# OUTPUT.net
KiCad netlist of a schematic drawn in Altium Designer
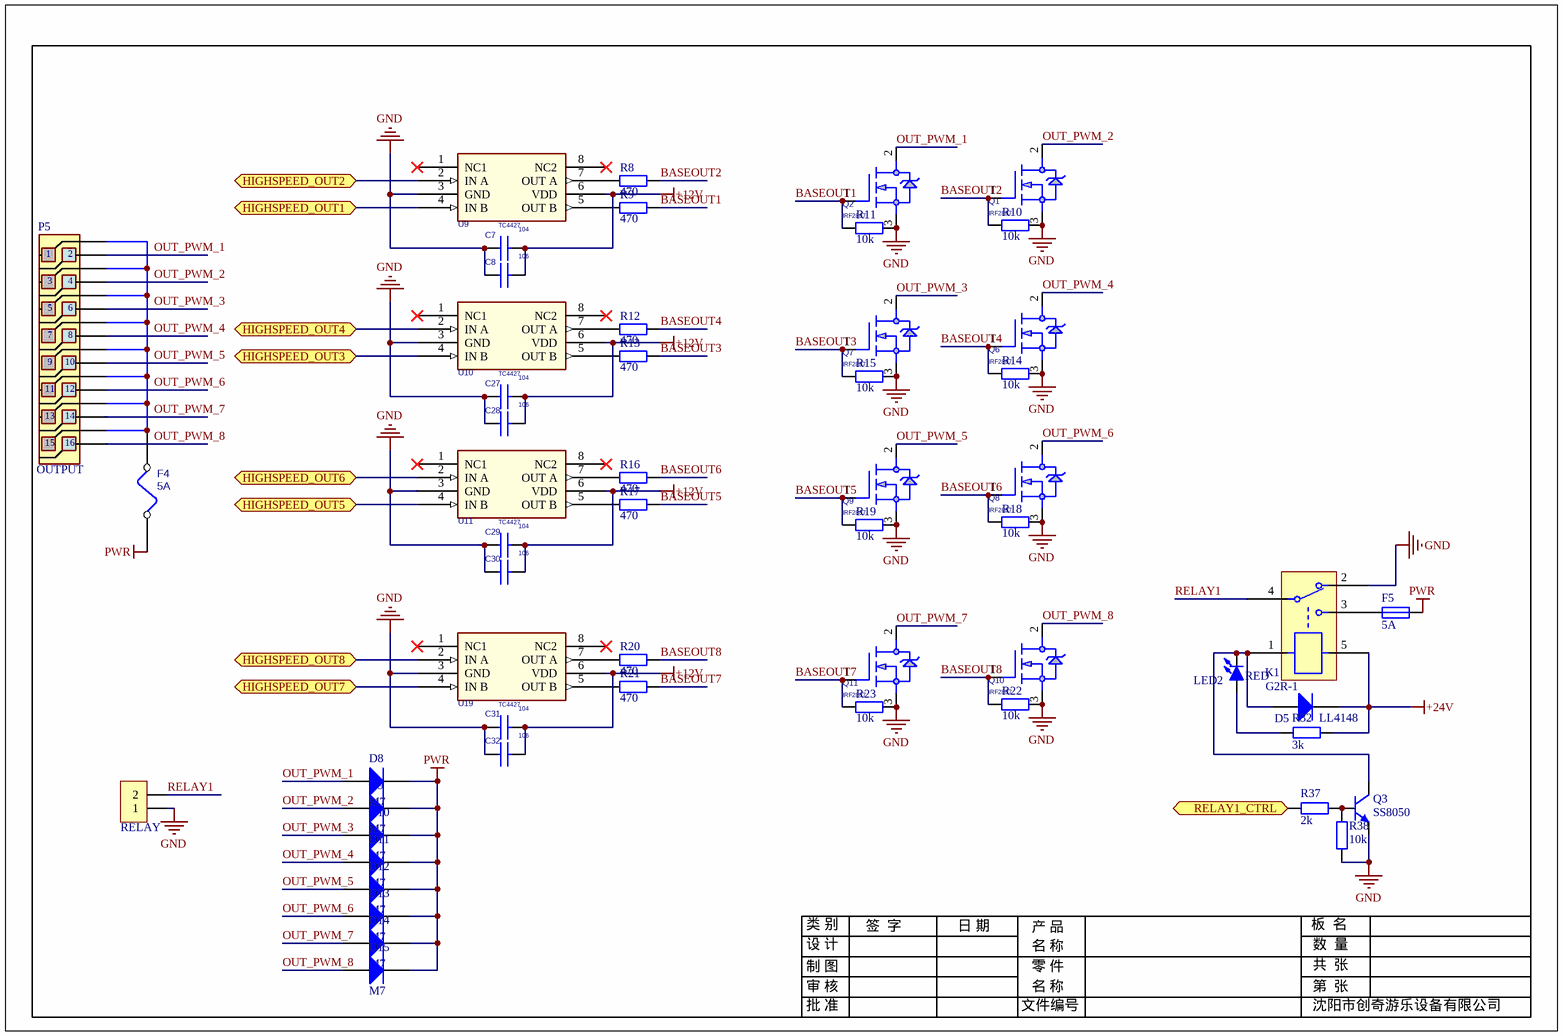
[diagram p0: OUTPUT.SchDoc]

(export (version "E")
  (design (tool "Eeschema 10.0.6"))
  (components
    (comp (ref "C7") (value "104") (footprint "C 0805") (libsource (lib "*") (part "CAP NP")))
    (comp (ref "C8") (value "106") (footprint "C 0805") (libsource (lib "*") (part "CAP NP")))
    (comp (ref "C27") (value "104") (footprint "C 0805") (libsource (lib "*") (part "CAP NP")))
    (comp (ref "C28") (value "106") (footprint "C 0805") (libsource (lib "*") (part "CAP NP")))
    (comp (ref "C29") (value "104") (footprint "C 0805") (libsource (lib "*") (part "CAP NP")))
    (comp (ref "C30") (value "106") (footprint "C 0805") (libsource (lib "*") (part "CAP NP")))
    (comp (ref "C31") (value "104") (footprint "C 0805") (libsource (lib "*") (part "CAP NP")))
    (comp (ref "C32") (value "106") (footprint "C 0805") (libsource (lib "*") (part "CAP NP")))
    (comp (ref "D5") (value "LL4148") (footprint "MINI_MELF (LL34)") (libsource (lib "any") (part "Diode")))
    (comp (ref "D8") (value "M7") (footprint "SMA") (libsource (lib "any") (part "Diode")))
    (comp (ref "D9") (value "M7") (footprint "SMA") (libsource (lib "any") (part "Diode")))
    (comp (ref "D10") (value "M7") (footprint "SMA") (libsource (lib "any") (part "Diode")))
    (comp (ref "D11") (value "M7") (footprint "SMA") (libsource (lib "any") (part "Diode")))
    (comp (ref "D12") (value "M7") (footprint "SMA") (libsource (lib "any") (part "Diode")))
    (comp (ref "D13") (value "M7") (footprint "SMA") (libsource (lib "any") (part "Diode")))
    (comp (ref "D14") (value "M7") (footprint "SMA") (libsource (lib "any") (part "Diode")))
    (comp (ref "D15") (value "M7") (footprint "SMA") (libsource (lib "any") (part "Diode")))
    (comp (ref "F4") (value "5A") (libsource (lib "*") (part "FUSE")))
    (comp (ref "F5")
      (value "5A")
      (footprint "FUSEe-CAR")
      (description "Fuse")
      (libsource (lib "*") (part "FUSE1"))
    )
    (comp (ref "K1") (value "G2R-1") (footprint "RELAY_OMRON_G2R") (libsource (lib "any") (part "Relay2")))
    (comp (ref "LED2")
      (value "RED")
      (footprint "LED 3MM-R")
      (description "贴片LED")
      (fields (field (name "版权归属") "源创客"))
      (libsource (lib "LED") (part "LED-SMD"))
    )
    (comp (ref "P5")
      (value "OUTPUT")
      (footprint "557-2x8")
      (description "接插件")
      (libsource (lib "Connectors") (part "557-2x8"))
    )
    (comp (ref "Q1") (value "IRF2807") (footprint "TO220A") (libsource (lib "*") (part "MOSFET N-Channel")))
    (comp (ref "Q2") (value "IRF2807") (footprint "TO220A") (libsource (lib "*") (part "MOSFET N-Channel")))
    (comp (ref "Q3")
      (value "SS8050")
      (footprint "SOT23-3N")
      (description "高频放大-NPN型")
      (fields (field (name "版权归属") "源创客"))
      (libsource (lib "三极管") (part "8050-SMD"))
    )
    (comp (ref "Q6") (value "IRF2807") (footprint "TO220A") (libsource (lib "*") (part "MOSFET N-Channel")))
    (comp (ref "Q7") (value "IRF2807") (footprint "TO220A") (libsource (lib "*") (part "MOSFET N-Channel")))
    (comp (ref "Q8") (value "IRF2807") (footprint "TO220A") (libsource (lib "*") (part "MOSFET N-Channel")))
    (comp (ref "Q9") (value "IRF2807") (footprint "TO220A") (libsource (lib "*") (part "MOSFET N-Channel")))
    (comp (ref "Q10") (value "IRF2807") (footprint "TO220A") (libsource (lib "*") (part "MOSFET N-Channel")))
    (comp (ref "Q11") (value "IRF2807") (footprint "TO220A") (libsource (lib "*") (part "MOSFET N-Channel")))
    (comp (ref "R8") (value "470") (footprint "R 0805") (libsource (lib "any") (part "Res1")))
    (comp (ref "R9") (value "470") (footprint "R 0805") (libsource (lib "any") (part "Res1")))
    (comp (ref "R10") (value "10k") (footprint "R 0805") (libsource (lib "any") (part "Res1")))
    (comp (ref "R11") (value "10k") (footprint "R 0805") (libsource (lib "any") (part "Res1")))
    (comp (ref "R12") (value "470") (footprint "R 0805") (libsource (lib "any") (part "Res1")))
    (comp (ref "R13") (value "470") (footprint "R 0805") (libsource (lib "any") (part "Res1")))
    (comp (ref "R14") (value "10k") (footprint "R 0805") (libsource (lib "any") (part "Res1")))
    (comp (ref "R15") (value "10k") (footprint "R 0805") (libsource (lib "any") (part "Res1")))
    (comp (ref "R16") (value "470") (footprint "R 0805") (libsource (lib "any") (part "Res1")))
    (comp (ref "R17") (value "470") (footprint "R 0805") (libsource (lib "any") (part "Res1")))
    (comp (ref "R18") (value "10k") (footprint "R 0805") (libsource (lib "any") (part "Res1")))
    (comp (ref "R19") (value "10k") (footprint "R 0805") (libsource (lib "any") (part "Res1")))
    (comp (ref "R20") (value "470") (footprint "R 0805") (libsource (lib "any") (part "Res1")))
    (comp (ref "R21") (value "470") (footprint "R 0805") (libsource (lib "any") (part "Res1")))
    (comp (ref "R22") (value "10k") (footprint "R 0805") (libsource (lib "any") (part "Res1")))
    (comp (ref "R23") (value "10k") (footprint "R 0805") (libsource (lib "any") (part "Res1")))
    (comp (ref "R32")
      (value "3k")
      (footprint "R 0805")
      (description "贴片电阻")
      (fields (field (name "版权归属") "源创客"))
      (libsource (lib "电阻-电容-电感") (part "R"))
    )
    (comp (ref "R37")
      (value "2k")
      (footprint "R 0805")
      (description "贴片电阻")
      (fields (field (name "版权归属") "源创客"))
      (libsource (lib "电阻-电容-电感") (part "R"))
    )
    (comp (ref "R38")
      (value "10k")
      (footprint "R 0805")
      (description "贴片电阻")
      (fields (field (name "版权归属") "源创客"))
      (libsource (lib "电阻-电容-电感") (part "R"))
    )
    (comp (ref "RELAY")
      (value "AUX")
      (footprint "557-2X1")
      (description "2P接插件")
      (fields (field (name "版权归属") "源创客"))
      (libsource (lib "接插件") (part "Header 2"))
    )
    (comp (ref "U9") (value "TC4427") (footprint "SO8") (libsource (lib "*") (part "TC4427EPA")))
    (comp (ref "U10") (value "TC4427") (footprint "SO8") (libsource (lib "*") (part "TC4427EPA")))
    (comp (ref "U11") (value "TC4427") (footprint "SO8") (libsource (lib "*") (part "TC4427EPA")))
    (comp (ref "U19") (value "TC4427") (footprint "SO8") (libsource (lib "*") (part "TC4427EPA")))
  )
  (nets
    (net (code "1") (name "+12V") (class "Default")
      (node (ref "C27") (pin "2") (pinfunction "2_2") (pintype "passive"))
      (node (ref "C28") (pin "2") (pinfunction "2_2") (pintype "passive"))
      (node (ref "C29") (pin "2") (pinfunction "2_2") (pintype "passive"))
      (node (ref "C30") (pin "2") (pinfunction "2_2") (pintype "passive"))
      (node (ref "C31") (pin "2") (pinfunction "2_2") (pintype "passive"))
      (node (ref "C32") (pin "2") (pinfunction "2_2") (pintype "passive"))
      (node (ref "C7") (pin "2") (pinfunction "2_2") (pintype "passive"))
      (node (ref "C8") (pin "2") (pinfunction "2_2") (pintype "passive"))
      (node (ref "U10") (pin "6") (pinfunction "VDD_6") (pintype "power_in"))
      (node (ref "U11") (pin "6") (pinfunction "VDD_6") (pintype "power_in"))
      (node (ref "U19") (pin "6") (pinfunction "VDD_6") (pintype "power_in"))
      (node (ref "U9") (pin "6") (pinfunction "VDD_6") (pintype "power_in"))
    )
    (net (code "2") (name "+24V") (class "Default")
      (node (ref "D5") (pin "2") (pinfunction "2_2") (pintype "passive"))
      (node (ref "K1") (pin "5") (pinfunction "5_5") (pintype "passive"))
      (node (ref "R32") (pin "1") (pinfunction "1_1") (pintype "passive"))
    )
    (net (code "3") (name "/BASEOUT1") (class "Default")
      (node (ref "Q2") (pin "1") (pinfunction "G_1") (pintype "passive"))
      (node (ref "R11") (pin "1") (pinfunction "1_1") (pintype "passive"))
      (node (ref "R9") (pin "2") (pinfunction "2_2") (pintype "passive"))
    )
    (net (code "4") (name "/BASEOUT2") (class "Default")
      (node (ref "Q1") (pin "1") (pinfunction "G_1") (pintype "passive"))
      (node (ref "R10") (pin "1") (pinfunction "1_1") (pintype "passive"))
      (node (ref "R8") (pin "2") (pinfunction "2_2") (pintype "passive"))
    )
    (net (code "5") (name "/BASEOUT3") (class "Default")
      (node (ref "Q7") (pin "1") (pinfunction "G_1") (pintype "passive"))
      (node (ref "R13") (pin "2") (pinfunction "2_2") (pintype "passive"))
      (node (ref "R15") (pin "1") (pinfunction "1_1") (pintype "passive"))
    )
    (net (code "6") (name "/BASEOUT4") (class "Default")
      (node (ref "Q6") (pin "1") (pinfunction "G_1") (pintype "passive"))
      (node (ref "R12") (pin "2") (pinfunction "2_2") (pintype "passive"))
      (node (ref "R14") (pin "1") (pinfunction "1_1") (pintype "passive"))
    )
    (net (code "7") (name "/BASEOUT5") (class "Default")
      (node (ref "Q9") (pin "1") (pinfunction "G_1") (pintype "passive"))
      (node (ref "R17") (pin "2") (pinfunction "2_2") (pintype "passive"))
      (node (ref "R19") (pin "1") (pinfunction "1_1") (pintype "passive"))
    )
    (net (code "8") (name "/BASEOUT6") (class "Default")
      (node (ref "Q8") (pin "1") (pinfunction "G_1") (pintype "passive"))
      (node (ref "R16") (pin "2") (pinfunction "2_2") (pintype "passive"))
      (node (ref "R18") (pin "1") (pinfunction "1_1") (pintype "passive"))
    )
    (net (code "9") (name "/BASEOUT7") (class "Default")
      (node (ref "Q11") (pin "1") (pinfunction "G_1") (pintype "passive"))
      (node (ref "R21") (pin "2") (pinfunction "2_2") (pintype "passive"))
      (node (ref "R23") (pin "1") (pinfunction "1_1") (pintype "passive"))
    )
    (net (code "10") (name "/BASEOUT8") (class "Default")
      (node (ref "Q10") (pin "1") (pinfunction "G_1") (pintype "passive"))
      (node (ref "R20") (pin "2") (pinfunction "2_2") (pintype "passive"))
      (node (ref "R22") (pin "1") (pinfunction "1_1") (pintype "passive"))
    )
    (net (code "11") (name "/HIGHSPEED_OUT1") (class "Default")
      (node (ref "U9") (pin "4") (pinfunction "IN_B_4") (pintype "input"))
    )
    (net (code "12") (name "/HIGHSPEED_OUT2") (class "Default")
      (node (ref "U9") (pin "2") (pinfunction "IN_A_2") (pintype "input"))
    )
    (net (code "13") (name "/HIGHSPEED_OUT3") (class "Default")
      (node (ref "U10") (pin "4") (pinfunction "IN_B_4") (pintype "input"))
    )
    (net (code "14") (name "/HIGHSPEED_OUT4") (class "Default")
      (node (ref "U10") (pin "2") (pinfunction "IN_A_2") (pintype "input"))
    )
    (net (code "15") (name "/HIGHSPEED_OUT5") (class "Default")
      (node (ref "U11") (pin "4") (pinfunction "IN_B_4") (pintype "input"))
    )
    (net (code "16") (name "/HIGHSPEED_OUT6") (class "Default")
      (node (ref "U11") (pin "2") (pinfunction "IN_A_2") (pintype "input"))
    )
    (net (code "17") (name "/HIGHSPEED_OUT7") (class "Default")
      (node (ref "U19") (pin "4") (pinfunction "IN_B_4") (pintype "input"))
    )
    (net (code "18") (name "/HIGHSPEED_OUT8") (class "Default")
      (node (ref "U19") (pin "2") (pinfunction "IN_A_2") (pintype "input"))
    )
    (net (code "19") (name "/OUT_PWM_1") (class "Default")
      (node (ref "D8") (pin "1") (pinfunction "1_1") (pintype "passive"))
      (node (ref "P5") (pin "2") (pinfunction "2_2") (pintype "passive"))
      (node (ref "Q2") (pin "2") (pinfunction "D_2") (pintype "passive"))
    )
    (net (code "20") (name "/OUT_PWM_2") (class "Default")
      (node (ref "D9") (pin "1") (pinfunction "1_1") (pintype "passive"))
      (node (ref "P5") (pin "4") (pinfunction "4_4") (pintype "passive"))
      (node (ref "Q1") (pin "2") (pinfunction "D_2") (pintype "passive"))
    )
    (net (code "21") (name "/OUT_PWM_3") (class "Default")
      (node (ref "D10") (pin "1") (pinfunction "1_1") (pintype "passive"))
      (node (ref "P5") (pin "6") (pinfunction "6_6") (pintype "passive"))
      (node (ref "Q7") (pin "2") (pinfunction "D_2") (pintype "passive"))
    )
    (net (code "22") (name "/OUT_PWM_4") (class "Default")
      (node (ref "D11") (pin "1") (pinfunction "1_1") (pintype "passive"))
      (node (ref "P5") (pin "8") (pinfunction "8_8") (pintype "passive"))
      (node (ref "Q6") (pin "2") (pinfunction "D_2") (pintype "passive"))
    )
    (net (code "23") (name "/OUT_PWM_5") (class "Default")
      (node (ref "D12") (pin "1") (pinfunction "1_1") (pintype "passive"))
      (node (ref "P5") (pin "10") (pinfunction "10_10") (pintype "passive"))
      (node (ref "Q9") (pin "2") (pinfunction "D_2") (pintype "passive"))
    )
    (net (code "24") (name "/OUT_PWM_6") (class "Default")
      (node (ref "D13") (pin "1") (pinfunction "1_1") (pintype "passive"))
      (node (ref "P5") (pin "12") (pinfunction "12_12") (pintype "passive"))
      (node (ref "Q8") (pin "2") (pinfunction "D_2") (pintype "passive"))
    )
    (net (code "25") (name "/OUT_PWM_7") (class "Default")
      (node (ref "D14") (pin "1") (pinfunction "1_1") (pintype "passive"))
      (node (ref "P5") (pin "14") (pinfunction "14_14") (pintype "passive"))
      (node (ref "Q11") (pin "2") (pinfunction "D_2") (pintype "passive"))
    )
    (net (code "26") (name "/OUT_PWM_8") (class "Default")
      (node (ref "D15") (pin "1") (pinfunction "1_1") (pintype "passive"))
      (node (ref "P5") (pin "16") (pinfunction "16_16") (pintype "passive"))
      (node (ref "Q10") (pin "2") (pinfunction "D_2") (pintype "passive"))
    )
    (net (code "27") (name "/RELAY1") (class "Default")
      (node (ref "K1") (pin "4") (pinfunction "4_4") (pintype "passive"))
      (node (ref "RELAY") (pin "2") (pinfunction "2_2") (pintype "passive"))
    )
    (net (code "28") (name "/RELAY1_CTRL") (class "Default")
      (node (ref "R37") (pin "2") (pinfunction "2_2") (pintype "passive"))
    )
    (net (code "29") (name "GND") (class "Default")
      (node (ref "C27") (pin "1") (pinfunction "1_1") (pintype "passive"))
      (node (ref "C28") (pin "1") (pinfunction "1_1") (pintype "passive"))
      (node (ref "C29") (pin "1") (pinfunction "1_1") (pintype "passive"))
      (node (ref "C30") (pin "1") (pinfunction "1_1") (pintype "passive"))
      (node (ref "C31") (pin "1") (pinfunction "1_1") (pintype "passive"))
      (node (ref "C32") (pin "1") (pinfunction "1_1") (pintype "passive"))
      (node (ref "C7") (pin "1") (pinfunction "1_1") (pintype "passive"))
      (node (ref "C8") (pin "1") (pinfunction "1_1") (pintype "passive"))
      (node (ref "K1") (pin "2") (pinfunction "2_2") (pintype "passive"))
      (node (ref "Q1") (pin "3") (pinfunction "S_3") (pintype "passive"))
      (node (ref "Q10") (pin "3") (pinfunction "S_3") (pintype "passive"))
      (node (ref "Q11") (pin "3") (pinfunction "S_3") (pintype "passive"))
      (node (ref "Q2") (pin "3") (pinfunction "S_3") (pintype "passive"))
      (node (ref "Q3") (pin "2") (pinfunction "E_2") (pintype "passive"))
      (node (ref "Q6") (pin "3") (pinfunction "S_3") (pintype "passive"))
      (node (ref "Q7") (pin "3") (pinfunction "S_3") (pintype "passive"))
      (node (ref "Q8") (pin "3") (pinfunction "S_3") (pintype "passive"))
      (node (ref "Q9") (pin "3") (pinfunction "S_3") (pintype "passive"))
      (node (ref "R10") (pin "2") (pinfunction "2_2") (pintype "passive"))
      (node (ref "R11") (pin "2") (pinfunction "2_2") (pintype "passive"))
      (node (ref "R14") (pin "2") (pinfunction "2_2") (pintype "passive"))
      (node (ref "R15") (pin "2") (pinfunction "2_2") (pintype "passive"))
      (node (ref "R18") (pin "2") (pinfunction "2_2") (pintype "passive"))
      (node (ref "R19") (pin "2") (pinfunction "2_2") (pintype "passive"))
      (node (ref "R22") (pin "2") (pinfunction "2_2") (pintype "passive"))
      (node (ref "R23") (pin "2") (pinfunction "2_2") (pintype "passive"))
      (node (ref "R38") (pin "2") (pinfunction "2_2") (pintype "passive"))
      (node (ref "RELAY") (pin "1") (pinfunction "1_1") (pintype "passive"))
      (node (ref "U10") (pin "3") (pinfunction "GND_3") (pintype "power_in"))
      (node (ref "U11") (pin "3") (pinfunction "GND_3") (pintype "power_in"))
      (node (ref "U19") (pin "3") (pinfunction "GND_3") (pintype "power_in"))
      (node (ref "U9") (pin "3") (pinfunction "GND_3") (pintype "power_in"))
    )
    (net (code "30") (name "Net-(F4-Pad2)") (class "Default")
      (node (ref "F4") (pin "2") (pinfunction "2_2") (pintype "passive"))
      (node (ref "P5") (pin "1") (pinfunction "1_1") (pintype "passive"))
      (node (ref "P5") (pin "11") (pinfunction "11_11") (pintype "passive"))
      (node (ref "P5") (pin "13") (pinfunction "13_13") (pintype "passive"))
      (node (ref "P5") (pin "15") (pinfunction "15_15") (pintype "passive"))
      (node (ref "P5") (pin "3") (pinfunction "3_3") (pintype "passive"))
      (node (ref "P5") (pin "5") (pinfunction "5_5") (pintype "passive"))
      (node (ref "P5") (pin "7") (pinfunction "7_7") (pintype "passive"))
      (node (ref "P5") (pin "9") (pinfunction "9_9") (pintype "passive"))
    )
    (net (code "31") (name "Net-(F5-Pad1)") (class "Default")
      (node (ref "F5") (pin "1") (pinfunction "1_1") (pintype "passive"))
      (node (ref "K1") (pin "3") (pinfunction "3_3") (pintype "passive"))
    )
    (net (code "32") (name "Net-(LED2-A)") (class "Default")
      (node (ref "LED2") (pin "1") (pinfunction "A_1") (pintype "passive"))
      (node (ref "R32") (pin "2") (pinfunction "2_2") (pintype "passive"))
    )
    (net (code "33") (name "Net-(LED2-K)") (class "Default")
      (node (ref "D5") (pin "1") (pinfunction "1_1") (pintype "passive"))
      (node (ref "K1") (pin "1") (pinfunction "1_1") (pintype "passive"))
      (node (ref "LED2") (pin "2") (pinfunction "K_2") (pintype "passive"))
      (node (ref "Q3") (pin "3") (pinfunction "C_3") (pintype "passive"))
    )
    (net (code "34") (name "Net-(Q3-B)") (class "Default")
      (node (ref "Q3") (pin "1") (pinfunction "B_1") (pintype "passive"))
      (node (ref "R37") (pin "1") (pinfunction "1_1") (pintype "passive"))
      (node (ref "R38") (pin "1") (pinfunction "1_1") (pintype "passive"))
    )
    (net (code "35") (name "Net-(U9-OUT_A)") (class "Default")
      (node (ref "R8") (pin "1") (pinfunction "1_1") (pintype "passive"))
      (node (ref "U9") (pin "7") (pinfunction "OUT_A_7") (pintype "output"))
    )
    (net (code "36") (name "Net-(U9-OUT_B)") (class "Default")
      (node (ref "R9") (pin "1") (pinfunction "1_1") (pintype "passive"))
      (node (ref "U9") (pin "5") (pinfunction "OUT_B_5") (pintype "output"))
    )
    (net (code "37") (name "Net-(U10-OUT_A)") (class "Default")
      (node (ref "R12") (pin "1") (pinfunction "1_1") (pintype "passive"))
      (node (ref "U10") (pin "7") (pinfunction "OUT_A_7") (pintype "output"))
    )
    (net (code "38") (name "Net-(U10-OUT_B)") (class "Default")
      (node (ref "R13") (pin "1") (pinfunction "1_1") (pintype "passive"))
      (node (ref "U10") (pin "5") (pinfunction "OUT_B_5") (pintype "output"))
    )
    (net (code "39") (name "Net-(U11-OUT_A)") (class "Default")
      (node (ref "R16") (pin "1") (pinfunction "1_1") (pintype "passive"))
      (node (ref "U11") (pin "7") (pinfunction "OUT_A_7") (pintype "output"))
    )
    (net (code "40") (name "Net-(U11-OUT_B)") (class "Default")
      (node (ref "R17") (pin "1") (pinfunction "1_1") (pintype "passive"))
      (node (ref "U11") (pin "5") (pinfunction "OUT_B_5") (pintype "output"))
    )
    (net (code "41") (name "Net-(U19-OUT_A)") (class "Default")
      (node (ref "R20") (pin "1") (pinfunction "1_1") (pintype "passive"))
      (node (ref "U19") (pin "7") (pinfunction "OUT_A_7") (pintype "output"))
    )
    (net (code "42") (name "Net-(U19-OUT_B)") (class "Default")
      (node (ref "R21") (pin "1") (pinfunction "1_1") (pintype "passive"))
      (node (ref "U19") (pin "5") (pinfunction "OUT_B_5") (pintype "output"))
    )
    (net (code "43") (name "PWR") (class "Default")
      (node (ref "D10") (pin "2") (pinfunction "2_2") (pintype "passive"))
      (node (ref "D11") (pin "2") (pinfunction "2_2") (pintype "passive"))
      (node (ref "D12") (pin "2") (pinfunction "2_2") (pintype "passive"))
      (node (ref "D13") (pin "2") (pinfunction "2_2") (pintype "passive"))
      (node (ref "D14") (pin "2") (pinfunction "2_2") (pintype "passive"))
      (node (ref "D15") (pin "2") (pinfunction "2_2") (pintype "passive"))
      (node (ref "D8") (pin "2") (pinfunction "2_2") (pintype "passive"))
      (node (ref "D9") (pin "2") (pinfunction "2_2") (pintype "passive"))
      (node (ref "F4") (pin "1") (pinfunction "1_1") (pintype "passive"))
      (node (ref "F5") (pin "2") (pinfunction "2_2") (pintype "passive"))
    )
    (net (code "44") (name "unconnected-(U9-NC1-Pad1)") (class "Default")
      (node (ref "U9") (pin "1") (pinfunction "NC1_1") (pintype "passive+no_connect"))
    )
    (net (code "45") (name "unconnected-(U9-NC2-Pad8)") (class "Default")
      (node (ref "U9") (pin "8") (pinfunction "NC2_8") (pintype "passive+no_connect"))
    )
    (net (code "46") (name "unconnected-(U10-NC1-Pad1)") (class "Default")
      (node (ref "U10") (pin "1") (pinfunction "NC1_1") (pintype "passive+no_connect"))
    )
    (net (code "47") (name "unconnected-(U10-NC2-Pad8)") (class "Default")
      (node (ref "U10") (pin "8") (pinfunction "NC2_8") (pintype "passive+no_connect"))
    )
    (net (code "48") (name "unconnected-(U11-NC1-Pad1)") (class "Default")
      (node (ref "U11") (pin "1") (pinfunction "NC1_1") (pintype "passive+no_connect"))
    )
    (net (code "49") (name "unconnected-(U11-NC2-Pad8)") (class "Default")
      (node (ref "U11") (pin "8") (pinfunction "NC2_8") (pintype "passive+no_connect"))
    )
    (net (code "50") (name "unconnected-(U19-NC1-Pad1)") (class "Default")
      (node (ref "U19") (pin "1") (pinfunction "NC1_1") (pintype "passive+no_connect"))
    )
    (net (code "51") (name "unconnected-(U19-NC2-Pad8)") (class "Default")
      (node (ref "U19") (pin "8") (pinfunction "NC2_8") (pintype "passive+no_connect"))
    )
  )
)
